# Breakout_ADS1299.net
KiCad netlist of a schematic drawn in EAGLE
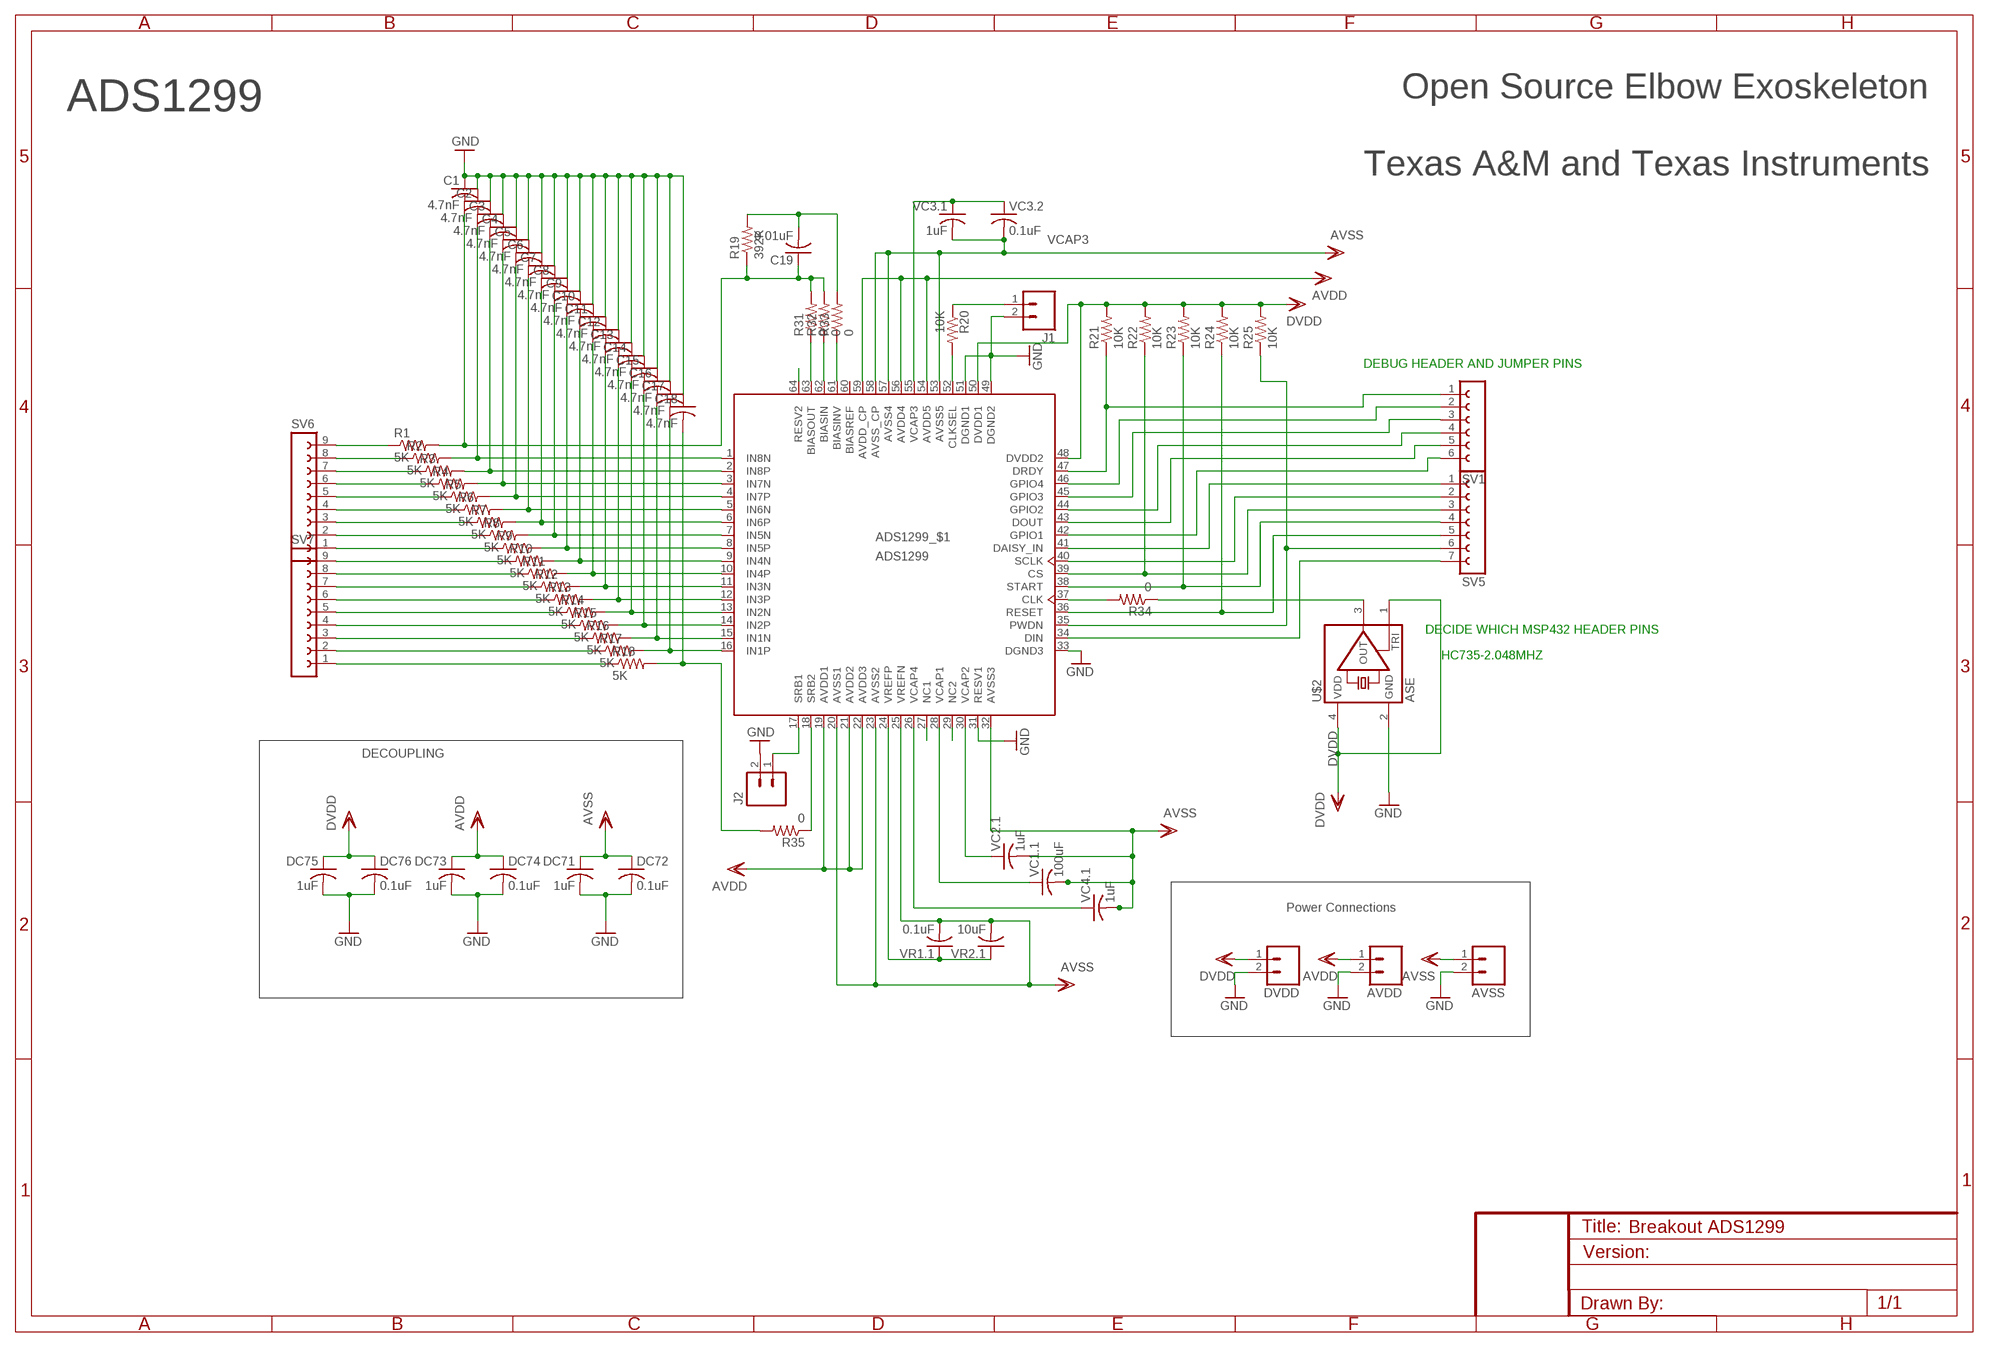
[diagram p0: schematic, sheet 1]

(export (version "E")
  (design (tool "Eeschema 10.0.6"))
  (components
    (comp (ref "ADS1")
      (value "ADS1299")
      (footprint "eagle-import:PAG_S-PQFP-G64")
      (fields (field (name "MF") "TEXAS INSTRUMENTS") (field (name "MPN") "ADS1299PAGR"))
      (libsource (lib "eagle-import") (part "ADS1299"))
    )
    (comp (ref "AVDD")
      (value "M025MM")
      (footprint "eagle-import:SCREWTERMINAL-5MM-2")
      (libsource (lib "eagle-import") (part "M025MM"))
    )
    (comp (ref "AVSS")
      (value "M025MM")
      (footprint "eagle-import:SCREWTERMINAL-5MM-2")
      (libsource (lib "eagle-import") (part "M025MM"))
    )
    (comp (ref "C1")
      (value "4.7nF")
      (footprint "eagle-import:C0603")
      (libsource (lib "eagle-import") (part "resistor_C-USC0603"))
    )
    (comp (ref "C2")
      (value "4.7nF")
      (footprint "eagle-import:C0603")
      (libsource (lib "eagle-import") (part "resistor_C-USC0603"))
    )
    (comp (ref "C3")
      (value "4.7nF")
      (footprint "eagle-import:C0603")
      (libsource (lib "eagle-import") (part "resistor_C-USC0603"))
    )
    (comp (ref "C4")
      (value "4.7nF")
      (footprint "eagle-import:C0603")
      (libsource (lib "eagle-import") (part "resistor_C-USC0603"))
    )
    (comp (ref "C5")
      (value "4.7nF")
      (footprint "eagle-import:C0603")
      (libsource (lib "eagle-import") (part "resistor_C-USC0603"))
    )
    (comp (ref "C6")
      (value "4.7nF")
      (footprint "eagle-import:C0603")
      (libsource (lib "eagle-import") (part "resistor_C-USC0603"))
    )
    (comp (ref "C7")
      (value "4.7nF")
      (footprint "eagle-import:C0603")
      (libsource (lib "eagle-import") (part "resistor_C-USC0603"))
    )
    (comp (ref "C8")
      (value "4.7nF")
      (footprint "eagle-import:C0603")
      (libsource (lib "eagle-import") (part "resistor_C-USC0603"))
    )
    (comp (ref "C9")
      (value "4.7nF")
      (footprint "eagle-import:C0603")
      (libsource (lib "eagle-import") (part "resistor_C-USC0603"))
    )
    (comp (ref "C10")
      (value "4.7nF")
      (footprint "eagle-import:C0603")
      (libsource (lib "eagle-import") (part "resistor_C-USC0603"))
    )
    (comp (ref "C11")
      (value "4.7nF")
      (footprint "eagle-import:C0603")
      (libsource (lib "eagle-import") (part "resistor_C-USC0603"))
    )
    (comp (ref "C12")
      (value "4.7nF")
      (footprint "eagle-import:C0603")
      (libsource (lib "eagle-import") (part "resistor_C-USC0603"))
    )
    (comp (ref "C13")
      (value "4.7nF")
      (footprint "eagle-import:C0603")
      (libsource (lib "eagle-import") (part "resistor_C-USC0603"))
    )
    (comp (ref "C14")
      (value "4.7nF")
      (footprint "eagle-import:C0603")
      (libsource (lib "eagle-import") (part "resistor_C-USC0603"))
    )
    (comp (ref "C15")
      (value "4.7nF")
      (footprint "eagle-import:C0603")
      (libsource (lib "eagle-import") (part "resistor_C-USC0603"))
    )
    (comp (ref "C16")
      (value "4.7nF")
      (footprint "eagle-import:C0603")
      (libsource (lib "eagle-import") (part "resistor_C-USC0603"))
    )
    (comp (ref "C17")
      (value "4.7nF")
      (footprint "eagle-import:C0603")
      (libsource (lib "eagle-import") (part "resistor_C-USC0603"))
    )
    (comp (ref "C18")
      (value "4.7nF")
      (footprint "eagle-import:C0603")
      (libsource (lib "eagle-import") (part "resistor_C-USC0603"))
    )
    (comp (ref "C19")
      (value "0.01uF")
      (footprint "eagle-import:C0603")
      (libsource (lib "eagle-import") (part "resistor_C-USC0603"))
    )
    (comp (ref "DC71")
      (value "1uF")
      (footprint "eagle-import:C0603")
      (libsource (lib "eagle-import") (part "C-USC0603"))
    )
    (comp (ref "DC72")
      (value "0.1uF")
      (footprint "eagle-import:C0603")
      (libsource (lib "eagle-import") (part "C-USC0603"))
    )
    (comp (ref "DC73")
      (value "1uF")
      (footprint "eagle-import:C0603")
      (libsource (lib "eagle-import") (part "C-USC0603"))
    )
    (comp (ref "DC74")
      (value "0.1uF")
      (footprint "eagle-import:C0603")
      (libsource (lib "eagle-import") (part "C-USC0603"))
    )
    (comp (ref "DC75")
      (value "1uF")
      (footprint "eagle-import:C0603")
      (libsource (lib "eagle-import") (part "C-USC0603"))
    )
    (comp (ref "DC76")
      (value "0.1uF")
      (footprint "eagle-import:C0603")
      (libsource (lib "eagle-import") (part "C-USC0603"))
    )
    (comp (ref "DVDD")
      (value "M025MM")
      (footprint "eagle-import:SCREWTERMINAL-5MM-2")
      (libsource (lib "eagle-import") (part "M025MM"))
    )
    (comp (ref "J1")
      (value "M02PTH")
      (footprint "eagle-import:1X02")
      (libsource (lib "eagle-import") (part "M02PTH"))
    )
    (comp (ref "J2")
      (value "M02PTH")
      (footprint "eagle-import:1X02")
      (libsource (lib "eagle-import") (part "M02PTH"))
    )
    (comp (ref "R1")
      (value "5K")
      (footprint "eagle-import:R0603")
      (libsource (lib "eagle-import") (part "R-US_R0603"))
    )
    (comp (ref "R2")
      (value "5K")
      (footprint "eagle-import:R0603")
      (libsource (lib "eagle-import") (part "R-US_R0603"))
    )
    (comp (ref "R3")
      (value "5K")
      (footprint "eagle-import:R0603")
      (libsource (lib "eagle-import") (part "R-US_R0603"))
    )
    (comp (ref "R4")
      (value "5K")
      (footprint "eagle-import:R0603")
      (libsource (lib "eagle-import") (part "R-US_R0603"))
    )
    (comp (ref "R5")
      (value "5K")
      (footprint "eagle-import:R0603")
      (libsource (lib "eagle-import") (part "R-US_R0603"))
    )
    (comp (ref "R6")
      (value "5K")
      (footprint "eagle-import:R0603")
      (libsource (lib "eagle-import") (part "R-US_R0603"))
    )
    (comp (ref "R7")
      (value "5K")
      (footprint "eagle-import:R0603")
      (libsource (lib "eagle-import") (part "R-US_R0603"))
    )
    (comp (ref "R8")
      (value "5K")
      (footprint "eagle-import:R0603")
      (libsource (lib "eagle-import") (part "R-US_R0603"))
    )
    (comp (ref "R9")
      (value "5K")
      (footprint "eagle-import:R0603")
      (libsource (lib "eagle-import") (part "R-US_R0603"))
    )
    (comp (ref "R10")
      (value "5K")
      (footprint "eagle-import:R0603")
      (libsource (lib "eagle-import") (part "R-US_R0603"))
    )
    (comp (ref "R11")
      (value "5K")
      (footprint "eagle-import:R0603")
      (libsource (lib "eagle-import") (part "R-US_R0603"))
    )
    (comp (ref "R12")
      (value "5K")
      (footprint "eagle-import:R0603")
      (libsource (lib "eagle-import") (part "R-US_R0603"))
    )
    (comp (ref "R13")
      (value "5K")
      (footprint "eagle-import:R0603")
      (libsource (lib "eagle-import") (part "R-US_R0603"))
    )
    (comp (ref "R14")
      (value "5K")
      (footprint "eagle-import:R0603")
      (libsource (lib "eagle-import") (part "R-US_R0603"))
    )
    (comp (ref "R15")
      (value "5K")
      (footprint "eagle-import:R0603")
      (libsource (lib "eagle-import") (part "R-US_R0603"))
    )
    (comp (ref "R16")
      (value "5K")
      (footprint "eagle-import:R0603")
      (libsource (lib "eagle-import") (part "R-US_R0603"))
    )
    (comp (ref "R17")
      (value "5K")
      (footprint "eagle-import:R0603")
      (libsource (lib "eagle-import") (part "R-US_R0603"))
    )
    (comp (ref "R18")
      (value "5K")
      (footprint "eagle-import:R0603")
      (libsource (lib "eagle-import") (part "R-US_R0603"))
    )
    (comp (ref "R19")
      (value "392K")
      (footprint "eagle-import:R0603")
      (libsource (lib "eagle-import") (part "R-US_R0603"))
    )
    (comp (ref "R20")
      (value "10K")
      (footprint "eagle-import:R0603")
      (libsource (lib "eagle-import") (part "R-US_R0603"))
    )
    (comp (ref "R21")
      (value "10K")
      (footprint "eagle-import:R0603")
      (libsource (lib "eagle-import") (part "R-US_R0603"))
    )
    (comp (ref "R22")
      (value "10K")
      (footprint "eagle-import:R0603")
      (libsource (lib "eagle-import") (part "R-US_R0603"))
    )
    (comp (ref "R23")
      (value "10K")
      (footprint "eagle-import:R0603")
      (libsource (lib "eagle-import") (part "R-US_R0603"))
    )
    (comp (ref "R24")
      (value "10K")
      (footprint "eagle-import:R0603")
      (libsource (lib "eagle-import") (part "R-US_R0603"))
    )
    (comp (ref "R25")
      (value "10K")
      (footprint "eagle-import:R0603")
      (libsource (lib "eagle-import") (part "R-US_R0603"))
    )
    (comp (ref "R31")
      (value "0")
      (footprint "eagle-import:R0603")
      (libsource (lib "eagle-import") (part "R-US_R0603"))
    )
    (comp (ref "R32")
      (value "0")
      (footprint "eagle-import:R0603")
      (libsource (lib "eagle-import") (part "R-US_R0603"))
    )
    (comp (ref "R33")
      (value "0")
      (footprint "eagle-import:R0603")
      (libsource (lib "eagle-import") (part "R-US_R0603"))
    )
    (comp (ref "R34")
      (value "0")
      (footprint "eagle-import:R0603")
      (libsource (lib "eagle-import") (part "R-US_R0603"))
    )
    (comp (ref "R35")
      (value "0")
      (footprint "eagle-import:R0603")
      (libsource (lib "eagle-import") (part "R-US_R0603"))
    )
    (comp (ref "SV1")
      (value "FE06-1")
      (footprint "eagle-import:FE06")
      (libsource (lib "eagle-import") (part "FE06-1"))
    )
    (comp (ref "SV5")
      (value "FE07-1")
      (footprint "eagle-import:FE07")
      (libsource (lib "eagle-import") (part "FE07-1"))
    )
    (comp (ref "SV6")
      (value "FE09-1")
      (footprint "eagle-import:FE09")
      (libsource (lib "eagle-import") (part "FE09-1"))
    )
    (comp (ref "SV7")
      (value "FE09-1")
      (footprint "eagle-import:FE09")
      (libsource (lib "eagle-import") (part "FE09-1"))
    )
    (comp (ref "U$2")
      (value "ASE")
      (footprint "eagle-import:ASE")
      (libsource (lib "eagle-import") (part "ASE"))
    )
    (comp (ref "VC1.1")
      (value "100uF")
      (footprint "eagle-import:C0603")
      (libsource (lib "eagle-import") (part "C-USC0603"))
    )
    (comp (ref "VC2.1")
      (value "1uF")
      (footprint "eagle-import:C0603")
      (libsource (lib "eagle-import") (part "resistor_C-USC0603"))
    )
    (comp (ref "VC3.1")
      (value "1uF")
      (footprint "eagle-import:C0603")
      (libsource (lib "eagle-import") (part "resistor_C-USC0603"))
    )
    (comp (ref "VC3.2")
      (value "0.1uF")
      (footprint "eagle-import:C0603")
      (libsource (lib "eagle-import") (part "resistor_C-USC0603"))
    )
    (comp (ref "VC4.1")
      (value "1uF")
      (footprint "eagle-import:C0603")
      (libsource (lib "eagle-import") (part "resistor_C-USC0603"))
    )
    (comp (ref "VR1.1")
      (value "0.1uF")
      (footprint "eagle-import:C0603")
      (libsource (lib "eagle-import") (part "resistor_C-USC0603"))
    )
    (comp (ref "VR2.1")
      (value "10uF")
      (footprint "eagle-import:C0603")
      (libsource (lib "eagle-import") (part "resistor_C-USC0603"))
    )
  )
  (nets
    (net (code "1") (name "AVDD") (class "Default")
      (node (ref "ADS1") (pin "19") (pinfunction "AVDD1_19") (pintype "power_in"))
      (node (ref "ADS1") (pin "21") (pinfunction "AVDD2_21") (pintype "power_in"))
      (node (ref "ADS1") (pin "22") (pinfunction "AVDD3_22") (pintype "power_in"))
      (node (ref "ADS1") (pin "54") (pinfunction "AVDD5_54") (pintype "power_in"))
      (node (ref "ADS1") (pin "56") (pinfunction "AVDD4_56") (pintype "power_in"))
      (node (ref "ADS1") (pin "59") (pinfunction "AVDD_CP_59") (pintype "power_in"))
      (node (ref "AVDD") (pin "1") (pinfunction "1_1") (pintype "passive"))
      (node (ref "DC73") (pin "1") (pinfunction "1_1") (pintype "passive"))
      (node (ref "DC74") (pin "1") (pinfunction "1_1") (pintype "passive"))
    )
    (net (code "2") (name "AVSS") (class "Default")
      (node (ref "ADS1") (pin "20") (pinfunction "AVSS1_20") (pintype "power_in"))
      (node (ref "ADS1") (pin "23") (pinfunction "AVSS2_23") (pintype "power_in"))
      (node (ref "ADS1") (pin "25") (pinfunction "VREFN_25") (pintype "input"))
      (node (ref "ADS1") (pin "32") (pinfunction "AVSS3_32") (pintype "power_in"))
      (node (ref "ADS1") (pin "53") (pinfunction "AVSS5_53") (pintype "power_in"))
      (node (ref "ADS1") (pin "57") (pinfunction "AVSS4_57") (pintype "power_in"))
      (node (ref "ADS1") (pin "58") (pinfunction "AVSS_CP_58") (pintype "power_in"))
      (node (ref "AVSS") (pin "1") (pinfunction "1_1") (pintype "passive"))
      (node (ref "DC71") (pin "1") (pinfunction "1_1") (pintype "passive"))
      (node (ref "DC72") (pin "1") (pinfunction "1_1") (pintype "passive"))
      (node (ref "VC1.1") (pin "2") (pinfunction "2_2") (pintype "passive"))
      (node (ref "VC2.1") (pin "2") (pinfunction "2_2") (pintype "passive"))
      (node (ref "VC3.1") (pin "2") (pinfunction "2_2") (pintype "passive"))
      (node (ref "VC3.2") (pin "2") (pinfunction "2_2") (pintype "passive"))
      (node (ref "VC4.1") (pin "2") (pinfunction "2_2") (pintype "passive"))
      (node (ref "VR1.1") (pin "2") (pinfunction "2_2") (pintype "passive"))
      (node (ref "VR2.1") (pin "2") (pinfunction "2_2") (pintype "passive"))
    )
    (net (code "3") (name "DVDD") (class "Default")
      (node (ref "ADS1") (pin "48") (pinfunction "DVDD2_48") (pintype "power_in"))
      (node (ref "ADS1") (pin "50") (pinfunction "DVDD1_50") (pintype "power_in"))
      (node (ref "DC75") (pin "1") (pinfunction "1_1") (pintype "passive"))
      (node (ref "DC76") (pin "1") (pinfunction "1_1") (pintype "passive"))
      (node (ref "DVDD") (pin "1") (pinfunction "1_1") (pintype "passive"))
      (node (ref "R21") (pin "2") (pinfunction "2_2") (pintype "passive"))
      (node (ref "R22") (pin "2") (pinfunction "2_2") (pintype "passive"))
      (node (ref "R23") (pin "2") (pinfunction "2_2") (pintype "passive"))
      (node (ref "R24") (pin "2") (pinfunction "2_2") (pintype "passive"))
      (node (ref "R25") (pin "2") (pinfunction "2_2") (pintype "passive"))
      (node (ref "U$2") (pin "1") (pinfunction "TRI_1") (pintype "input"))
      (node (ref "U$2") (pin "4") (pinfunction "VDD_4") (pintype "power_in"))
    )
    (net (code "4") (name "GND") (class "Default")
      (node (ref "ADS1") (pin "31") (pinfunction "RESV1_31") (pintype "input"))
      (node (ref "ADS1") (pin "33") (pinfunction "DGND3_33") (pintype "power_in"))
      (node (ref "ADS1") (pin "49") (pinfunction "DGND2_49") (pintype "power_in"))
      (node (ref "ADS1") (pin "51") (pinfunction "DGND1_51") (pintype "power_in"))
      (node (ref "AVDD") (pin "2") (pinfunction "2_2") (pintype "passive"))
      (node (ref "AVSS") (pin "2") (pinfunction "2_2") (pintype "passive"))
      (node (ref "C1") (pin "1") (pinfunction "1_1") (pintype "passive"))
      (node (ref "C10") (pin "1") (pinfunction "1_1") (pintype "passive"))
      (node (ref "C11") (pin "1") (pinfunction "1_1") (pintype "passive"))
      (node (ref "C12") (pin "1") (pinfunction "1_1") (pintype "passive"))
      (node (ref "C13") (pin "1") (pinfunction "1_1") (pintype "passive"))
      (node (ref "C14") (pin "1") (pinfunction "1_1") (pintype "passive"))
      (node (ref "C15") (pin "1") (pinfunction "1_1") (pintype "passive"))
      (node (ref "C16") (pin "1") (pinfunction "1_1") (pintype "passive"))
      (node (ref "C17") (pin "1") (pinfunction "1_1") (pintype "passive"))
      (node (ref "C18") (pin "1") (pinfunction "1_1") (pintype "passive"))
      (node (ref "C2") (pin "1") (pinfunction "1_1") (pintype "passive"))
      (node (ref "C3") (pin "1") (pinfunction "1_1") (pintype "passive"))
      (node (ref "C4") (pin "1") (pinfunction "1_1") (pintype "passive"))
      (node (ref "C5") (pin "1") (pinfunction "1_1") (pintype "passive"))
      (node (ref "C6") (pin "1") (pinfunction "1_1") (pintype "passive"))
      (node (ref "C7") (pin "1") (pinfunction "1_1") (pintype "passive"))
      (node (ref "C8") (pin "1") (pinfunction "1_1") (pintype "passive"))
      (node (ref "C9") (pin "1") (pinfunction "1_1") (pintype "passive"))
      (node (ref "DC71") (pin "2") (pinfunction "2_2") (pintype "passive"))
      (node (ref "DC72") (pin "2") (pinfunction "2_2") (pintype "passive"))
      (node (ref "DC73") (pin "2") (pinfunction "2_2") (pintype "passive"))
      (node (ref "DC74") (pin "2") (pinfunction "2_2") (pintype "passive"))
      (node (ref "DC75") (pin "2") (pinfunction "2_2") (pintype "passive"))
      (node (ref "DC76") (pin "2") (pinfunction "2_2") (pintype "passive"))
      (node (ref "DVDD") (pin "2") (pinfunction "2_2") (pintype "passive"))
      (node (ref "J1") (pin "2") (pinfunction "2_2") (pintype "passive"))
      (node (ref "J2") (pin "2") (pinfunction "2_2") (pintype "passive"))
      (node (ref "U$2") (pin "2") (pinfunction "GND_2") (pintype "power_in"))
    )
    (net (code "5") (name "Net-(ADS1-BIASIN)") (class "Default")
      (node (ref "ADS1") (pin "62") (pinfunction "BIASIN_62") (pintype "input"))
      (node (ref "R32") (pin "1") (pinfunction "1_1") (pintype "passive"))
    )
    (net (code "6") (name "Net-(ADS1-BIASINV)") (class "Default")
      (node (ref "ADS1") (pin "61") (pinfunction "BIASINV_61") (pintype "bidirectional"))
      (node (ref "R33") (pin "1") (pinfunction "1_1") (pintype "passive"))
    )
    (net (code "7") (name "Net-(ADS1-BIASOUT)") (class "Default")
      (node (ref "ADS1") (pin "63") (pinfunction "BIASOUT_63") (pintype "output"))
      (node (ref "R31") (pin "1") (pinfunction "1_1") (pintype "passive"))
    )
    (net (code "8") (name "Net-(ADS1-CLK)") (class "Default")
      (node (ref "ADS1") (pin "37") (pinfunction "CLK_37") (pintype "bidirectional"))
      (node (ref "R34") (pin "2") (pinfunction "2_2") (pintype "passive"))
    )
    (net (code "9") (name "Net-(ADS1-CLKSEL)") (class "Default")
      (node (ref "ADS1") (pin "52") (pinfunction "CLKSEL_52") (pintype "input"))
      (node (ref "R20") (pin "2") (pinfunction "2_2") (pintype "passive"))
    )
    (net (code "10") (name "Net-(ADS1-CS)") (class "Default")
      (node (ref "ADS1") (pin "39") (pinfunction "CS_39") (pintype "input"))
      (node (ref "R22") (pin "1") (pinfunction "1_1") (pintype "passive"))
      (node (ref "SV5") (pin "3") (pinfunction "3_3") (pintype "passive"))
    )
    (net (code "11") (name "Net-(ADS1-DAISY_IN)") (class "Default")
      (node (ref "ADS1") (pin "41") (pinfunction "DAISY_IN_41") (pintype "input"))
      (node (ref "SV5") (pin "1") (pinfunction "1_1") (pintype "passive"))
    )
    (net (code "12") (name "Net-(ADS1-DIN)") (class "Default")
      (node (ref "ADS1") (pin "34") (pinfunction "DIN_34") (pintype "input"))
      (node (ref "SV5") (pin "7") (pinfunction "7_7") (pintype "passive"))
    )
    (net (code "13") (name "Net-(ADS1-DOUT)") (class "Default")
      (node (ref "ADS1") (pin "43") (pinfunction "DOUT_43") (pintype "output"))
      (node (ref "SV1") (pin "5") (pinfunction "5_5") (pintype "passive"))
    )
    (net (code "14") (name "Net-(ADS1-DRDY)") (class "Default")
      (node (ref "ADS1") (pin "47") (pinfunction "DRDY_47") (pintype "output"))
      (node (ref "R21") (pin "1") (pinfunction "1_1") (pintype "passive"))
      (node (ref "SV1") (pin "1") (pinfunction "1_1") (pintype "passive"))
    )
    (net (code "15") (name "Net-(ADS1-GPIO1)") (class "Default")
      (node (ref "ADS1") (pin "42") (pinfunction "GPIO1_42") (pintype "bidirectional"))
      (node (ref "SV1") (pin "6") (pinfunction "6_6") (pintype "passive"))
    )
    (net (code "16") (name "Net-(ADS1-GPIO2)") (class "Default")
      (node (ref "ADS1") (pin "44") (pinfunction "GPIO2_44") (pintype "bidirectional"))
      (node (ref "SV1") (pin "4") (pinfunction "4_4") (pintype "passive"))
    )
    (net (code "17") (name "Net-(ADS1-GPIO3)") (class "Default")
      (node (ref "ADS1") (pin "45") (pinfunction "GPIO3_45") (pintype "bidirectional"))
      (node (ref "SV1") (pin "3") (pinfunction "3_3") (pintype "passive"))
    )
    (net (code "18") (name "Net-(ADS1-GPIO4)") (class "Default")
      (node (ref "ADS1") (pin "46") (pinfunction "GPIO4_46") (pintype "bidirectional"))
      (node (ref "SV1") (pin "2") (pinfunction "2_2") (pintype "passive"))
    )
    (net (code "19") (name "Net-(ADS1-IN1N)") (class "Default")
      (node (ref "ADS1") (pin "15") (pinfunction "IN1N_15") (pintype "input"))
      (node (ref "C16") (pin "2") (pinfunction "2_2") (pintype "passive"))
      (node (ref "R16") (pin "2") (pinfunction "2_2") (pintype "passive"))
    )
    (net (code "20") (name "Net-(ADS1-IN1P)") (class "Default")
      (node (ref "ADS1") (pin "16") (pinfunction "IN1P_16") (pintype "input"))
      (node (ref "C17") (pin "2") (pinfunction "2_2") (pintype "passive"))
      (node (ref "R17") (pin "2") (pinfunction "2_2") (pintype "passive"))
    )
    (net (code "21") (name "Net-(ADS1-IN2N)") (class "Default")
      (node (ref "ADS1") (pin "13") (pinfunction "IN2N_13") (pintype "input"))
      (node (ref "C14") (pin "2") (pinfunction "2_2") (pintype "passive"))
      (node (ref "R14") (pin "2") (pinfunction "2_2") (pintype "passive"))
    )
    (net (code "22") (name "Net-(ADS1-IN2P)") (class "Default")
      (node (ref "ADS1") (pin "14") (pinfunction "IN2P_14") (pintype "input"))
      (node (ref "C15") (pin "2") (pinfunction "2_2") (pintype "passive"))
      (node (ref "R15") (pin "2") (pinfunction "2_2") (pintype "passive"))
    )
    (net (code "23") (name "Net-(ADS1-IN3N)") (class "Default")
      (node (ref "ADS1") (pin "11") (pinfunction "IN3N_11") (pintype "input"))
      (node (ref "C12") (pin "2") (pinfunction "2_2") (pintype "passive"))
      (node (ref "R12") (pin "2") (pinfunction "2_2") (pintype "passive"))
    )
    (net (code "24") (name "Net-(ADS1-IN3P)") (class "Default")
      (node (ref "ADS1") (pin "12") (pinfunction "IN3P_12") (pintype "input"))
      (node (ref "C13") (pin "2") (pinfunction "2_2") (pintype "passive"))
      (node (ref "R13") (pin "2") (pinfunction "2_2") (pintype "passive"))
    )
    (net (code "25") (name "Net-(ADS1-IN4N)") (class "Default")
      (node (ref "ADS1") (pin "9") (pinfunction "IN4N_9") (pintype "input"))
      (node (ref "C10") (pin "2") (pinfunction "2_2") (pintype "passive"))
      (node (ref "R10") (pin "2") (pinfunction "2_2") (pintype "passive"))
    )
    (net (code "26") (name "Net-(ADS1-IN4P)") (class "Default")
      (node (ref "ADS1") (pin "10") (pinfunction "IN4P_10") (pintype "input"))
      (node (ref "C11") (pin "2") (pinfunction "2_2") (pintype "passive"))
      (node (ref "R11") (pin "2") (pinfunction "2_2") (pintype "passive"))
    )
    (net (code "27") (name "Net-(ADS1-IN5N)") (class "Default")
      (node (ref "ADS1") (pin "7") (pinfunction "IN5N_7") (pintype "input"))
      (node (ref "C8") (pin "2") (pinfunction "2_2") (pintype "passive"))
      (node (ref "R8") (pin "2") (pinfunction "2_2") (pintype "passive"))
    )
    (net (code "28") (name "Net-(ADS1-IN5P)") (class "Default")
      (node (ref "ADS1") (pin "8") (pinfunction "IN5P_8") (pintype "input"))
      (node (ref "C9") (pin "2") (pinfunction "2_2") (pintype "passive"))
      (node (ref "R9") (pin "2") (pinfunction "2_2") (pintype "passive"))
    )
    (net (code "29") (name "Net-(ADS1-IN6N)") (class "Default")
      (node (ref "ADS1") (pin "5") (pinfunction "IN6N_5") (pintype "input"))
      (node (ref "C6") (pin "2") (pinfunction "2_2") (pintype "passive"))
      (node (ref "R6") (pin "2") (pinfunction "2_2") (pintype "passive"))
    )
    (net (code "30") (name "Net-(ADS1-IN6P)") (class "Default")
      (node (ref "ADS1") (pin "6") (pinfunction "IN6P_6") (pintype "input"))
      (node (ref "C7") (pin "2") (pinfunction "2_2") (pintype "passive"))
      (node (ref "R7") (pin "2") (pinfunction "2_2") (pintype "passive"))
    )
    (net (code "31") (name "Net-(ADS1-IN7N)") (class "Default")
      (node (ref "ADS1") (pin "3") (pinfunction "IN7N_3") (pintype "input"))
      (node (ref "C4") (pin "2") (pinfunction "2_2") (pintype "passive"))
      (node (ref "R4") (pin "2") (pinfunction "2_2") (pintype "passive"))
    )
    (net (code "32") (name "Net-(ADS1-IN7P)") (class "Default")
      (node (ref "ADS1") (pin "4") (pinfunction "IN7P_4") (pintype "input"))
      (node (ref "C5") (pin "2") (pinfunction "2_2") (pintype "passive"))
      (node (ref "R5") (pin "2") (pinfunction "2_2") (pintype "passive"))
    )
    (net (code "33") (name "Net-(ADS1-IN8N)") (class "Default")
      (node (ref "ADS1") (pin "1") (pinfunction "IN8N_1") (pintype "input"))
      (node (ref "C2") (pin "2") (pinfunction "2_2") (pintype "passive"))
      (node (ref "R2") (pin "2") (pinfunction "2_2") (pintype "passive"))
    )
    (net (code "34") (name "Net-(ADS1-IN8P)") (class "Default")
      (node (ref "ADS1") (pin "2") (pinfunction "IN8P_2") (pintype "input"))
      (node (ref "C3") (pin "2") (pinfunction "2_2") (pintype "passive"))
      (node (ref "R3") (pin "2") (pinfunction "2_2") (pintype "passive"))
    )
    (net (code "35") (name "Net-(ADS1-PWDN)") (class "Default")
      (node (ref "ADS1") (pin "35") (pinfunction "PWDN_35") (pintype "input"))
      (node (ref "R25") (pin "1") (pinfunction "1_1") (pintype "passive"))
      (node (ref "SV5") (pin "6") (pinfunction "6_6") (pintype "passive"))
    )
    (net (code "36") (name "Net-(ADS1-RESET)") (class "Default")
      (node (ref "ADS1") (pin "36") (pinfunction "RESET_36") (pintype "input"))
      (node (ref "R24") (pin "1") (pinfunction "1_1") (pintype "passive"))
      (node (ref "SV5") (pin "5") (pinfunction "5_5") (pintype "passive"))
    )
    (net (code "37") (name "Net-(ADS1-SCLK)") (class "Default")
      (node (ref "ADS1") (pin "40") (pinfunction "SCLK_40") (pintype "input"))
      (node (ref "SV5") (pin "2") (pinfunction "2_2") (pintype "passive"))
    )
    (net (code "38") (name "Net-(ADS1-SRB1)") (class "Default")
      (node (ref "ADS1") (pin "17") (pinfunction "SRB1_17") (pintype "bidirectional"))
      (node (ref "J2") (pin "1") (pinfunction "1_1") (pintype "passive"))
    )
    (net (code "39") (name "Net-(ADS1-SRB2)") (class "Default")
      (node (ref "ADS1") (pin "18") (pinfunction "SRB2_18") (pintype "bidirectional"))
      (node (ref "R35") (pin "1") (pinfunction "1_1") (pintype "passive"))
    )
    (net (code "40") (name "Net-(ADS1-START)") (class "Default")
      (node (ref "ADS1") (pin "38") (pinfunction "START_38") (pintype "input"))
      (node (ref "R23") (pin "1") (pinfunction "1_1") (pintype "passive"))
      (node (ref "SV5") (pin "4") (pinfunction "4_4") (pintype "passive"))
    )
    (net (code "41") (name "Net-(ADS1-VCAP1)") (class "Default")
      (node (ref "ADS1") (pin "28") (pinfunction "VCAP1_28") (pintype "passive"))
      (node (ref "VC1.1") (pin "1") (pinfunction "1_1") (pintype "passive"))
    )
    (net (code "42") (name "Net-(ADS1-VCAP2)") (class "Default")
      (node (ref "ADS1") (pin "30") (pinfunction "VCAP2_30") (pintype "passive"))
      (node (ref "VC2.1") (pin "1") (pinfunction "1_1") (pintype "passive"))
    )
    (net (code "43") (name "Net-(ADS1-VCAP3)") (class "Default")
      (node (ref "ADS1") (pin "55") (pinfunction "VCAP3_55") (pintype "passive"))
      (node (ref "VC3.1") (pin "1") (pinfunction "1_1") (pintype "passive"))
      (node (ref "VC3.2") (pin "1") (pinfunction "1_1") (pintype "passive"))
    )
    (net (code "44") (name "Net-(ADS1-VCAP4)") (class "Default")
      (node (ref "ADS1") (pin "26") (pinfunction "VCAP4_26") (pintype "output"))
      (node (ref "VC4.1") (pin "1") (pinfunction "1_1") (pintype "passive"))
    )
    (net (code "45") (name "Net-(ADS1-VREFP)") (class "Default")
      (node (ref "ADS1") (pin "24") (pinfunction "VREFP_24") (pintype "bidirectional"))
      (node (ref "VR1.1") (pin "1") (pinfunction "1_1") (pintype "passive"))
      (node (ref "VR2.1") (pin "1") (pinfunction "1_1") (pintype "passive"))
    )
    (net (code "46") (name "Net-(C1-Pad2)") (class "Default")
      (node (ref "C1") (pin "2") (pinfunction "2_2") (pintype "passive"))
      (node (ref "C19") (pin "1") (pinfunction "1_1") (pintype "passive"))
      (node (ref "R1") (pin "2") (pinfunction "2_2") (pintype "passive"))
      (node (ref "R19") (pin "1") (pinfunction "1_1") (pintype "passive"))
      (node (ref "R31") (pin "2") (pinfunction "2_2") (pintype "passive"))
      (node (ref "R32") (pin "2") (pinfunction "2_2") (pintype "passive"))
    )
    (net (code "47") (name "Net-(C18-Pad2)") (class "Default")
      (node (ref "C18") (pin "2") (pinfunction "2_2") (pintype "passive"))
      (node (ref "R18") (pin "2") (pinfunction "2_2") (pintype "passive"))
      (node (ref "R35") (pin "2") (pinfunction "2_2") (pintype "passive"))
    )
    (net (code "48") (name "Net-(C19-Pad2)") (class "Default")
      (node (ref "C19") (pin "2") (pinfunction "2_2") (pintype "passive"))
      (node (ref "R19") (pin "2") (pinfunction "2_2") (pintype "passive"))
      (node (ref "R33") (pin "2") (pinfunction "2_2") (pintype "passive"))
    )
    (net (code "49") (name "Net-(J1-Pad1)") (class "Default")
      (node (ref "J1") (pin "1") (pinfunction "1_1") (pintype "passive"))
      (node (ref "R20") (pin "1") (pinfunction "1_1") (pintype "passive"))
    )
    (net (code "50") (name "Net-(R1-Pad1)") (class "Default")
      (node (ref "R1") (pin "1") (pinfunction "1_1") (pintype "passive"))
      (node (ref "SV6") (pin "9") (pinfunction "9_9") (pintype "passive"))
    )
    (net (code "51") (name "Net-(R2-Pad1)") (class "Default")
      (node (ref "R2") (pin "1") (pinfunction "1_1") (pintype "passive"))
      (node (ref "SV6") (pin "8") (pinfunction "8_8") (pintype "passive"))
    )
    (net (code "52") (name "Net-(R3-Pad1)") (class "Default")
      (node (ref "R3") (pin "1") (pinfunction "1_1") (pintype "passive"))
      (node (ref "SV6") (pin "7") (pinfunction "7_7") (pintype "passive"))
    )
    (net (code "53") (name "Net-(R4-Pad1)") (class "Default")
      (node (ref "R4") (pin "1") (pinfunction "1_1") (pintype "passive"))
      (node (ref "SV6") (pin "6") (pinfunction "6_6") (pintype "passive"))
    )
    (net (code "54") (name "Net-(R5-Pad1)") (class "Default")
      (node (ref "R5") (pin "1") (pinfunction "1_1") (pintype "passive"))
      (node (ref "SV6") (pin "5") (pinfunction "5_5") (pintype "passive"))
    )
    (net (code "55") (name "Net-(R6-Pad1)") (class "Default")
      (node (ref "R6") (pin "1") (pinfunction "1_1") (pintype "passive"))
      (node (ref "SV6") (pin "4") (pinfunction "4_4") (pintype "passive"))
    )
    (net (code "56") (name "Net-(R7-Pad1)") (class "Default")
      (node (ref "R7") (pin "1") (pinfunction "1_1") (pintype "passive"))
      (node (ref "SV6") (pin "3") (pinfunction "3_3") (pintype "passive"))
    )
    (net (code "57") (name "Net-(R8-Pad1)") (class "Default")
      (node (ref "R8") (pin "1") (pinfunction "1_1") (pintype "passive"))
      (node (ref "SV6") (pin "2") (pinfunction "2_2") (pintype "passive"))
    )
    (net (code "58") (name "Net-(R9-Pad1)") (class "Default")
      (node (ref "R9") (pin "1") (pinfunction "1_1") (pintype "passive"))
      (node (ref "SV6") (pin "1") (pinfunction "1_1") (pintype "passive"))
    )
    (net (code "59") (name "Net-(R10-Pad1)") (class "Default")
      (node (ref "R10") (pin "1") (pinfunction "1_1") (pintype "passive"))
      (node (ref "SV7") (pin "9") (pinfunction "9_9") (pintype "passive"))
    )
    (net (code "60") (name "Net-(R11-Pad1)") (class "Default")
      (node (ref "R11") (pin "1") (pinfunction "1_1") (pintype "passive"))
      (node (ref "SV7") (pin "8") (pinfunction "8_8") (pintype "passive"))
    )
    (net (code "61") (name "Net-(R12-Pad1)") (class "Default")
      (node (ref "R12") (pin "1") (pinfunction "1_1") (pintype "passive"))
      (node (ref "SV7") (pin "7") (pinfunction "7_7") (pintype "passive"))
    )
    (net (code "62") (name "Net-(R13-Pad1)") (class "Default")
      (node (ref "R13") (pin "1") (pinfunction "1_1") (pintype "passive"))
      (node (ref "SV7") (pin "6") (pinfunction "6_6") (pintype "passive"))
    )
    (net (code "63") (name "Net-(R14-Pad1)") (class "Default")
      (node (ref "R14") (pin "1") (pinfunction "1_1") (pintype "passive"))
      (node (ref "SV7") (pin "5") (pinfunction "5_5") (pintype "passive"))
    )
    (net (code "64") (name "Net-(R15-Pad1)") (class "Default")
      (node (ref "R15") (pin "1") (pinfunction "1_1") (pintype "passive"))
      (node (ref "SV7") (pin "4") (pinfunction "4_4") (pintype "passive"))
    )
    (net (code "65") (name "Net-(R16-Pad1)") (class "Default")
      (node (ref "R16") (pin "1") (pinfunction "1_1") (pintype "passive"))
      (node (ref "SV7") (pin "3") (pinfunction "3_3") (pintype "passive"))
    )
    (net (code "66") (name "Net-(R17-Pad1)") (class "Default")
      (node (ref "R17") (pin "1") (pinfunction "1_1") (pintype "passive"))
      (node (ref "SV7") (pin "2") (pinfunction "2_2") (pintype "passive"))
    )
    (net (code "67") (name "Net-(R18-Pad1)") (class "Default")
      (node (ref "R18") (pin "1") (pinfunction "1_1") (pintype "passive"))
      (node (ref "SV7") (pin "1") (pinfunction "1_1") (pintype "passive"))
    )
    (net (code "68") (name "Net-(U$2-OUT)") (class "Default")
      (node (ref "R34") (pin "1") (pinfunction "1_1") (pintype "passive"))
      (node (ref "U$2") (pin "3") (pinfunction "OUT_3") (pintype "output"))
    )
    (net (code "69") (name "unconnected-(ADS1-BIASREF-Pad60)") (class "Default")
      (node (ref "ADS1") (pin "60") (pinfunction "BIASREF_60") (pintype "input"))
    )
    (net (code "70") (name "unconnected-(ADS1-NC1-Pad27)") (class "Default")
      (node (ref "ADS1") (pin "27") (pinfunction "NC1_27") (pintype "no_connect"))
    )
    (net (code "71") (name "unconnected-(ADS1-NC2-Pad29)") (class "Default")
      (node (ref "ADS1") (pin "29") (pinfunction "NC2_29") (pintype "no_connect"))
    )
    (net (code "72") (name "unconnected-(ADS1-RESV2-Pad64)") (class "Default")
      (node (ref "ADS1") (pin "64") (pinfunction "RESV2_64") (pintype "no_connect"))
    )
  )
)
